# rpiSensors.net
KiCad netlist of a schematic drawn in EAGLE
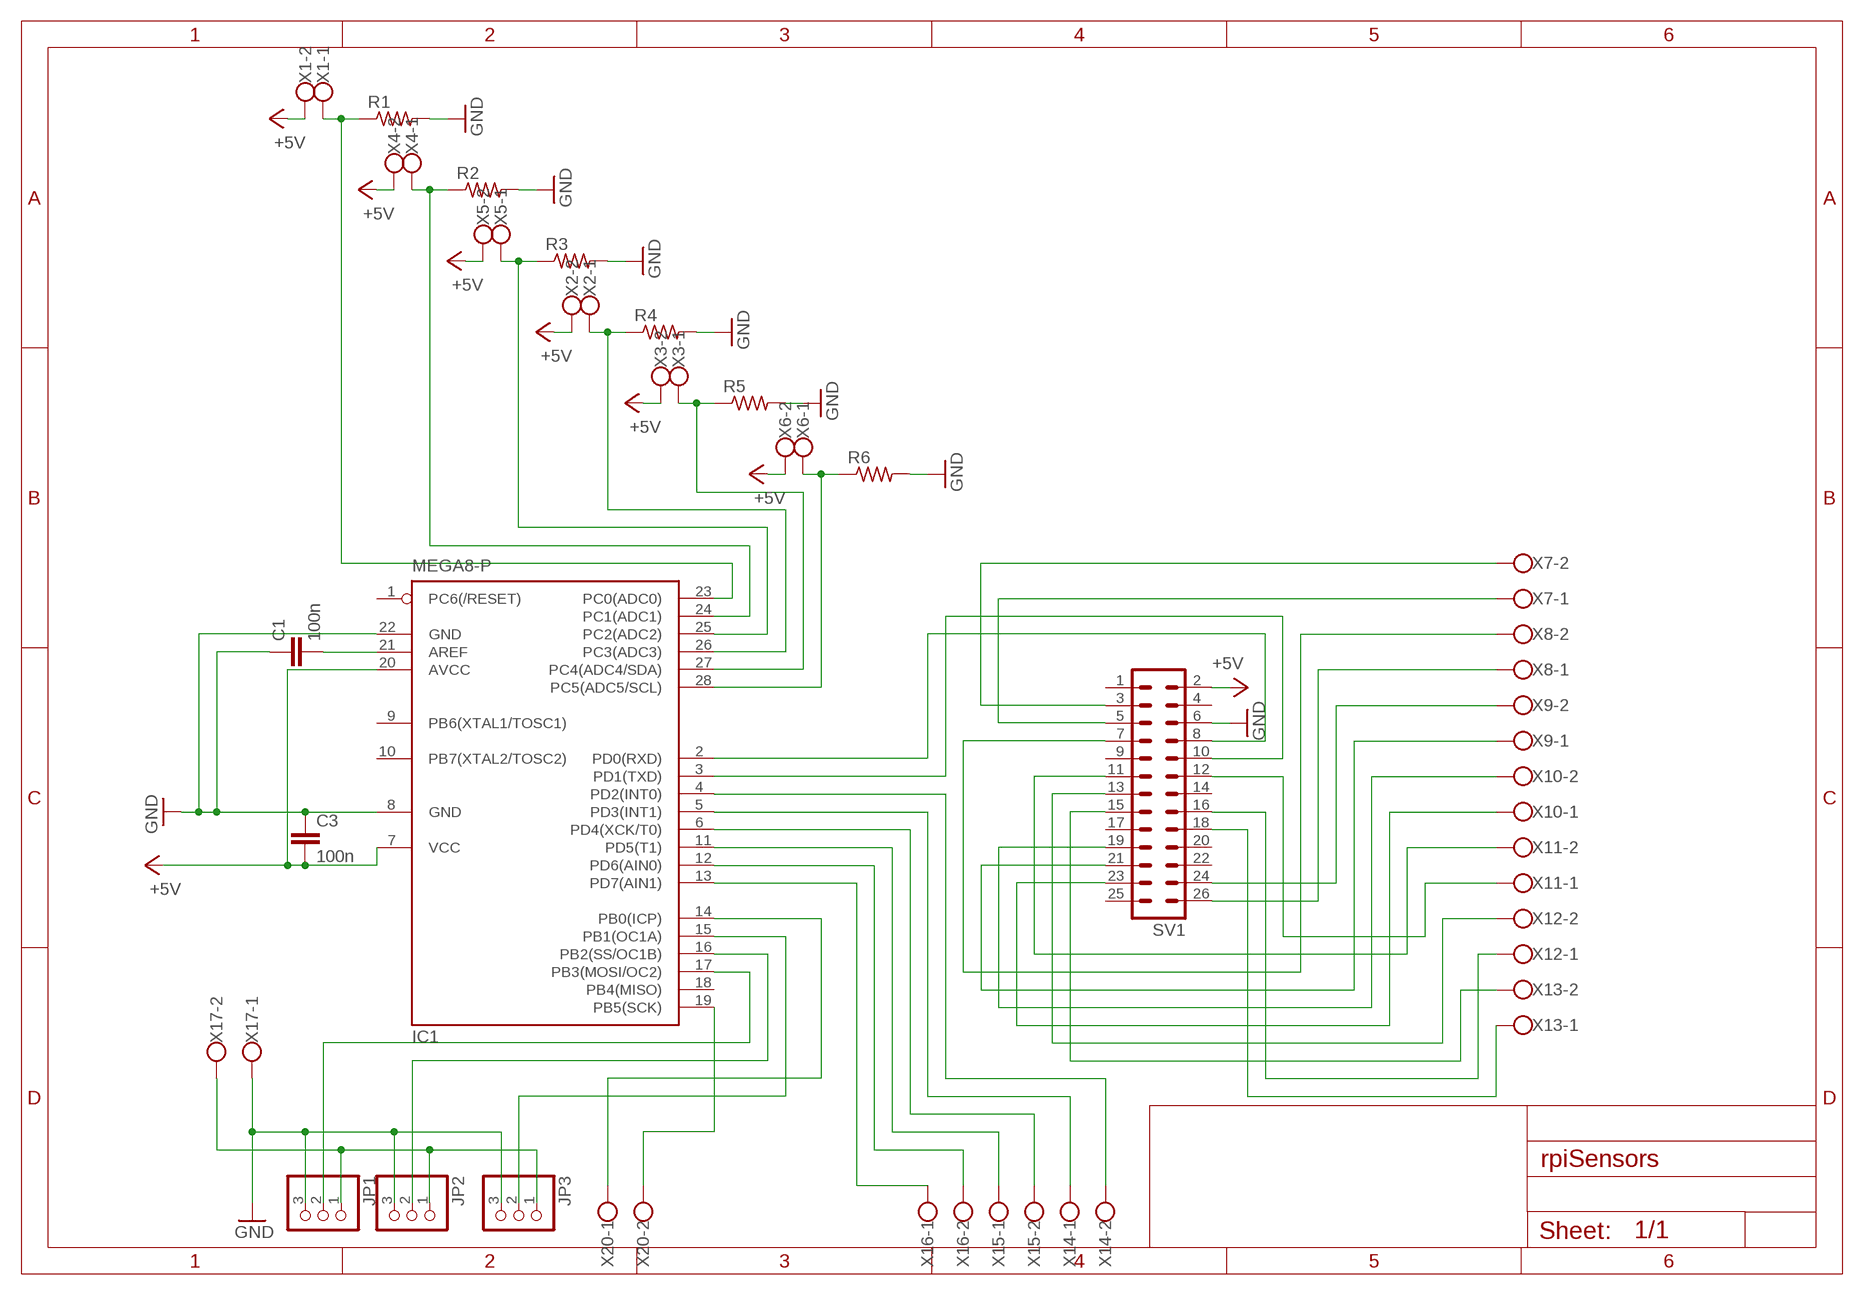
[diagram p0: schematic, sheet 1]

(export (version "E")
  (design (tool "Eeschema 10.0.6"))
  (components
    (comp (ref "C1")
      (value "100n")
      (footprint "eagle-import:C2.5-3")
      (libsource (lib "eagle-import") (part "C2,5-3"))
    )
    (comp (ref "C3")
      (value "100n")
      (footprint "eagle-import:C2.5-3")
      (libsource (lib "eagle-import") (part "C2,5-3"))
    )
    (comp (ref "IC1")
      (value "MEGA8-P")
      (footprint "eagle-import:DIL28-3")
      (libsource (lib "eagle-import") (part "MEGA8-P"))
    )
    (comp (ref "JP1")
      (value "PINHD-1X3")
      (footprint "eagle-import:1X03")
      (libsource (lib "eagle-import") (part "PINHD-1X3"))
    )
    (comp (ref "JP2")
      (value "PINHD-1X3")
      (footprint "eagle-import:1X03")
      (libsource (lib "eagle-import") (part "PINHD-1X3"))
    )
    (comp (ref "JP3")
      (value "PINHD-1X3")
      (footprint "eagle-import:1X03")
      (libsource (lib "eagle-import") (part "PINHD-1X3"))
    )
    (comp (ref "R1")
      (value "R-US_0309/12")
      (footprint "eagle-import:0309_12")
      (libsource (lib "eagle-import") (part "R-US_0309/12"))
    )
    (comp (ref "R2")
      (value "R-US_0309/12")
      (footprint "eagle-import:0309_12")
      (libsource (lib "eagle-import") (part "R-US_0309/12"))
    )
    (comp (ref "R3")
      (value "R-US_0309/12")
      (footprint "eagle-import:0309_12")
      (libsource (lib "eagle-import") (part "R-US_0309/12"))
    )
    (comp (ref "R4")
      (value "R-US_0309/12")
      (footprint "eagle-import:0309_12")
      (libsource (lib "eagle-import") (part "R-US_0309/12"))
    )
    (comp (ref "R5")
      (value "R-US_0309/12")
      (footprint "eagle-import:0309_12")
      (libsource (lib "eagle-import") (part "R-US_0309/12"))
    )
    (comp (ref "R6")
      (value "R-US_0309/12")
      (footprint "eagle-import:0309_12")
      (libsource (lib "eagle-import") (part "R-US_0309/12"))
    )
    (comp (ref "SV1")
      (value "ML26")
      (footprint "eagle-import:ML26")
      (libsource (lib "eagle-import") (part "ML26"))
    )
    (comp (ref "X1")
      (value "W237-102")
      (footprint "eagle-import:W237-102")
      (fields (field (name "MPN") "237-102"))
      (libsource (lib "eagle-import") (part "W237-102"))
    )
    (comp (ref "X2")
      (value "W237-102")
      (footprint "eagle-import:W237-102")
      (fields (field (name "MPN") "237-102"))
      (libsource (lib "eagle-import") (part "W237-102"))
    )
    (comp (ref "X3")
      (value "W237-102")
      (footprint "eagle-import:W237-102")
      (fields (field (name "MPN") "237-102"))
      (libsource (lib "eagle-import") (part "W237-102"))
    )
    (comp (ref "X4")
      (value "W237-102")
      (footprint "eagle-import:W237-102")
      (fields (field (name "MPN") "237-102"))
      (libsource (lib "eagle-import") (part "W237-102"))
    )
    (comp (ref "X5")
      (value "W237-102")
      (footprint "eagle-import:W237-102")
      (fields (field (name "MPN") "237-102"))
      (libsource (lib "eagle-import") (part "W237-102"))
    )
    (comp (ref "X6")
      (value "W237-102")
      (footprint "eagle-import:W237-102")
      (fields (field (name "MPN") "237-102"))
      (libsource (lib "eagle-import") (part "W237-102"))
    )
    (comp (ref "X7")
      (value "W237-102")
      (footprint "eagle-import:W237-102")
      (fields (field (name "MPN") "237-102"))
      (libsource (lib "eagle-import") (part "W237-102"))
    )
    (comp (ref "X8")
      (value "W237-102")
      (footprint "eagle-import:W237-102")
      (fields (field (name "MPN") "237-102"))
      (libsource (lib "eagle-import") (part "W237-102"))
    )
    (comp (ref "X9")
      (value "W237-102")
      (footprint "eagle-import:W237-102")
      (fields (field (name "MPN") "237-102"))
      (libsource (lib "eagle-import") (part "W237-102"))
    )
    (comp (ref "X10")
      (value "W237-102")
      (footprint "eagle-import:W237-102")
      (fields (field (name "MPN") "237-102"))
      (libsource (lib "eagle-import") (part "W237-102"))
    )
    (comp (ref "X11")
      (value "W237-102")
      (footprint "eagle-import:W237-102")
      (fields (field (name "MPN") "237-102"))
      (libsource (lib "eagle-import") (part "W237-102"))
    )
    (comp (ref "X12")
      (value "W237-102")
      (footprint "eagle-import:W237-102")
      (fields (field (name "MPN") "237-102"))
      (libsource (lib "eagle-import") (part "W237-102"))
    )
    (comp (ref "X13")
      (value "W237-102")
      (footprint "eagle-import:W237-102")
      (fields (field (name "MPN") "237-102"))
      (libsource (lib "eagle-import") (part "W237-102"))
    )
    (comp (ref "X14")
      (value "W237-102")
      (footprint "eagle-import:W237-102")
      (fields (field (name "MPN") "237-102"))
      (libsource (lib "eagle-import") (part "W237-102"))
    )
    (comp (ref "X15")
      (value "W237-102")
      (footprint "eagle-import:W237-102")
      (fields (field (name "MPN") "237-102"))
      (libsource (lib "eagle-import") (part "W237-102"))
    )
    (comp (ref "X16")
      (value "W237-102")
      (footprint "eagle-import:W237-102")
      (fields (field (name "MPN") "237-102"))
      (libsource (lib "eagle-import") (part "W237-102"))
    )
    (comp (ref "X17")
      (value "W237-102")
      (footprint "eagle-import:W237-102")
      (fields (field (name "MPN") "237-102"))
      (libsource (lib "eagle-import") (part "W237-102"))
    )
    (comp (ref "X20")
      (value "W237-102")
      (footprint "eagle-import:W237-102")
      (fields (field (name "MPN") "237-102"))
      (libsource (lib "eagle-import") (part "W237-102"))
    )
  )
  (nets
    (net (code "1") (name "+5V") (class "Default")
      (node (ref "C3") (pin "2") (pinfunction "2_2") (pintype "passive"))
      (node (ref "IC1") (pin "20") (pinfunction "AVCC_20") (pintype "power_in"))
      (node (ref "IC1") (pin "7") (pinfunction "VCC_7") (pintype "power_in"))
      (node (ref "SV1") (pin "2") (pinfunction "2_2") (pintype "passive"))
      (node (ref "X1") (pin "2") (pinfunction "KL_2") (pintype "passive"))
      (node (ref "X2") (pin "2") (pinfunction "KL_2") (pintype "passive"))
      (node (ref "X3") (pin "2") (pinfunction "KL_2") (pintype "passive"))
      (node (ref "X4") (pin "2") (pinfunction "KL_2") (pintype "passive"))
      (node (ref "X5") (pin "2") (pinfunction "KL_2") (pintype "passive"))
      (node (ref "X6") (pin "2") (pinfunction "KL_2") (pintype "passive"))
    )
    (net (code "2") (name "GND") (class "Default")
      (node (ref "C1") (pin "1") (pinfunction "1_1") (pintype "passive"))
      (node (ref "C3") (pin "1") (pinfunction "1_1") (pintype "passive"))
      (node (ref "IC1") (pin "22") (pinfunction "GND_22") (pintype "power_in"))
      (node (ref "IC1") (pin "8") (pinfunction "GND_8") (pintype "power_in"))
      (node (ref "JP1") (pin "3") (pinfunction "3_3") (pintype "passive"))
      (node (ref "JP2") (pin "3") (pinfunction "3_3") (pintype "passive"))
      (node (ref "JP3") (pin "3") (pinfunction "3_3") (pintype "passive"))
      (node (ref "R1") (pin "2") (pinfunction "2_2") (pintype "passive"))
      (node (ref "R2") (pin "2") (pinfunction "2_2") (pintype "passive"))
      (node (ref "R3") (pin "2") (pinfunction "2_2") (pintype "passive"))
      (node (ref "R4") (pin "2") (pinfunction "2_2") (pintype "passive"))
      (node (ref "R5") (pin "2") (pinfunction "2_2") (pintype "passive"))
      (node (ref "R6") (pin "2") (pinfunction "2_2") (pintype "passive"))
      (node (ref "SV1") (pin "6") (pinfunction "6_6") (pintype "passive"))
      (node (ref "X17") (pin "1") (pinfunction "KL_1") (pintype "passive"))
    )
    (net (code "3") (name "Net-(IC1-AREF)") (class "Default")
      (node (ref "C1") (pin "2") (pinfunction "2_2") (pintype "passive"))
      (node (ref "IC1") (pin "21") (pinfunction "AREF_21") (pintype "passive"))
    )
    (net (code "4") (name "Net-(IC1-PB0(ICP))") (class "Default")
      (node (ref "IC1") (pin "14") (pinfunction "PB0(ICP)_14") (pintype "bidirectional"))
      (node (ref "X20") (pin "1") (pinfunction "KL_1") (pintype "passive"))
    )
    (net (code "5") (name "Net-(IC1-PB1(OC1A))") (class "Default")
      (node (ref "IC1") (pin "15") (pinfunction "PB1(OC1A)_15") (pintype "bidirectional"))
      (node (ref "JP3") (pin "2") (pinfunction "2_2") (pintype "passive"))
    )
    (net (code "6") (name "Net-(IC1-PB2(SS{slash}OC1B))") (class "Default")
      (node (ref "IC1") (pin "16") (pinfunction "PB2(SS/OC1B)_16") (pintype "bidirectional"))
      (node (ref "JP2") (pin "2") (pinfunction "2_2") (pintype "passive"))
    )
    (net (code "7") (name "Net-(IC1-PB3(MOSI{slash}OC2))") (class "Default")
      (node (ref "IC1") (pin "17") (pinfunction "PB3(MOSI/OC2)_17") (pintype "bidirectional"))
      (node (ref "JP1") (pin "2") (pinfunction "2_2") (pintype "passive"))
    )
    (net (code "8") (name "Net-(IC1-PB5(SCK))") (class "Default")
      (node (ref "IC1") (pin "19") (pinfunction "PB5(SCK)_19") (pintype "bidirectional"))
      (node (ref "X20") (pin "2") (pinfunction "KL_2") (pintype "passive"))
    )
    (net (code "9") (name "Net-(IC1-PC0(ADC0))") (class "Default")
      (node (ref "IC1") (pin "23") (pinfunction "PC0(ADC0)_23") (pintype "bidirectional"))
      (node (ref "R1") (pin "1") (pinfunction "1_1") (pintype "passive"))
      (node (ref "X1") (pin "1") (pinfunction "KL_1") (pintype "passive"))
    )
    (net (code "10") (name "Net-(IC1-PC1(ADC1))") (class "Default")
      (node (ref "IC1") (pin "24") (pinfunction "PC1(ADC1)_24") (pintype "bidirectional"))
      (node (ref "R2") (pin "1") (pinfunction "1_1") (pintype "passive"))
      (node (ref "X4") (pin "1") (pinfunction "KL_1") (pintype "passive"))
    )
    (net (code "11") (name "Net-(IC1-PC2(ADC2))") (class "Default")
      (node (ref "IC1") (pin "25") (pinfunction "PC2(ADC2)_25") (pintype "bidirectional"))
      (node (ref "R3") (pin "1") (pinfunction "1_1") (pintype "passive"))
      (node (ref "X5") (pin "1") (pinfunction "KL_1") (pintype "passive"))
    )
    (net (code "12") (name "Net-(IC1-PC3(ADC3))") (class "Default")
      (node (ref "IC1") (pin "26") (pinfunction "PC3(ADC3)_26") (pintype "bidirectional"))
      (node (ref "R4") (pin "1") (pinfunction "1_1") (pintype "passive"))
      (node (ref "X2") (pin "1") (pinfunction "KL_1") (pintype "passive"))
    )
    (net (code "13") (name "Net-(IC1-PC4(ADC4{slash}SDA))") (class "Default")
      (node (ref "IC1") (pin "27") (pinfunction "PC4(ADC4/SDA)_27") (pintype "bidirectional"))
      (node (ref "R5") (pin "1") (pinfunction "1_1") (pintype "passive"))
      (node (ref "X3") (pin "1") (pinfunction "KL_1") (pintype "passive"))
    )
    (net (code "14") (name "Net-(IC1-PC5(ADC5{slash}SCL))") (class "Default")
      (node (ref "IC1") (pin "28") (pinfunction "PC5(ADC5/SCL)_28") (pintype "bidirectional"))
      (node (ref "R6") (pin "1") (pinfunction "1_1") (pintype "passive"))
      (node (ref "X6") (pin "1") (pinfunction "KL_1") (pintype "passive"))
    )
    (net (code "15") (name "Net-(IC1-PD0(RXD))") (class "Default")
      (node (ref "IC1") (pin "2") (pinfunction "PD0(RXD)_2") (pintype "bidirectional"))
      (node (ref "SV1") (pin "8") (pinfunction "8_8") (pintype "passive"))
    )
    (net (code "16") (name "Net-(IC1-PD1(TXD))") (class "Default")
      (node (ref "IC1") (pin "3") (pinfunction "PD1(TXD)_3") (pintype "bidirectional"))
      (node (ref "SV1") (pin "10") (pinfunction "10_10") (pintype "passive"))
    )
    (net (code "17") (name "Net-(IC1-PD2(INT0))") (class "Default")
      (node (ref "IC1") (pin "4") (pinfunction "PD2(INT0)_4") (pintype "bidirectional"))
      (node (ref "X14") (pin "2") (pinfunction "KL_2") (pintype "passive"))
    )
    (net (code "18") (name "Net-(IC1-PD3(INT1))") (class "Default")
      (node (ref "IC1") (pin "5") (pinfunction "PD3(INT1)_5") (pintype "bidirectional"))
      (node (ref "X14") (pin "1") (pinfunction "KL_1") (pintype "passive"))
    )
    (net (code "19") (name "Net-(IC1-PD4(XCK{slash}T0))") (class "Default")
      (node (ref "IC1") (pin "6") (pinfunction "PD4(XCK/T0)_6") (pintype "bidirectional"))
      (node (ref "X15") (pin "2") (pinfunction "KL_2") (pintype "passive"))
    )
    (net (code "20") (name "Net-(IC1-PD5(T1))") (class "Default")
      (node (ref "IC1") (pin "11") (pinfunction "PD5(T1)_11") (pintype "bidirectional"))
      (node (ref "X15") (pin "1") (pinfunction "KL_1") (pintype "passive"))
    )
    (net (code "21") (name "Net-(IC1-PD6(AIN0))") (class "Default")
      (node (ref "IC1") (pin "12") (pinfunction "PD6(AIN0)_12") (pintype "bidirectional"))
      (node (ref "X16") (pin "2") (pinfunction "KL_2") (pintype "passive"))
    )
    (net (code "22") (name "Net-(IC1-PD7(AIN1))") (class "Default")
      (node (ref "IC1") (pin "13") (pinfunction "PD7(AIN1)_13") (pintype "bidirectional"))
      (node (ref "X16") (pin "1") (pinfunction "KL_1") (pintype "passive"))
    )
    (net (code "23") (name "Net-(X7A-KL)") (class "Default")
      (node (ref "SV1") (pin "5") (pinfunction "5_5") (pintype "passive"))
      (node (ref "X7") (pin "1") (pinfunction "KL_1") (pintype "passive"))
    )
    (net (code "24") (name "Net-(X7B-KL)") (class "Default")
      (node (ref "SV1") (pin "3") (pinfunction "3_3") (pintype "passive"))
      (node (ref "X7") (pin "2") (pinfunction "KL_2") (pintype "passive"))
    )
    (net (code "25") (name "Net-(X8A-KL)") (class "Default")
      (node (ref "SV1") (pin "26") (pinfunction "26_26") (pintype "passive"))
      (node (ref "X8") (pin "1") (pinfunction "KL_1") (pintype "passive"))
    )
    (net (code "26") (name "Net-(X8B-KL)") (class "Default")
      (node (ref "SV1") (pin "7") (pinfunction "7_7") (pintype "passive"))
      (node (ref "X8") (pin "2") (pinfunction "KL_2") (pintype "passive"))
    )
    (net (code "27") (name "Net-(X9A-KL)") (class "Default")
      (node (ref "SV1") (pin "21") (pinfunction "21_21") (pintype "passive"))
      (node (ref "X9") (pin "1") (pinfunction "KL_1") (pintype "passive"))
    )
    (net (code "28") (name "Net-(X9B-KL)") (class "Default")
      (node (ref "SV1") (pin "24") (pinfunction "24_24") (pintype "passive"))
      (node (ref "X9") (pin "2") (pinfunction "KL_2") (pintype "passive"))
    )
    (net (code "29") (name "Net-(X10A-KL)") (class "Default")
      (node (ref "SV1") (pin "23") (pinfunction "23_23") (pintype "passive"))
      (node (ref "X10") (pin "1") (pinfunction "KL_1") (pintype "passive"))
    )
    (net (code "30") (name "Net-(X10B-KL)") (class "Default")
      (node (ref "SV1") (pin "19") (pinfunction "19_19") (pintype "passive"))
      (node (ref "X10") (pin "2") (pinfunction "KL_2") (pintype "passive"))
    )
    (net (code "31") (name "Net-(X11A-KL)") (class "Default")
      (node (ref "SV1") (pin "12") (pinfunction "12_12") (pintype "passive"))
      (node (ref "X11") (pin "1") (pinfunction "KL_1") (pintype "passive"))
    )
    (net (code "32") (name "Net-(X11B-KL)") (class "Default")
      (node (ref "SV1") (pin "11") (pinfunction "11_11") (pintype "passive"))
      (node (ref "X11") (pin "2") (pinfunction "KL_2") (pintype "passive"))
    )
    (net (code "33") (name "Net-(X12A-KL)") (class "Default")
      (node (ref "SV1") (pin "16") (pinfunction "16_16") (pintype "passive"))
      (node (ref "X12") (pin "1") (pinfunction "KL_1") (pintype "passive"))
    )
    (net (code "34") (name "Net-(X12B-KL)") (class "Default")
      (node (ref "SV1") (pin "13") (pinfunction "13_13") (pintype "passive"))
      (node (ref "X12") (pin "2") (pinfunction "KL_2") (pintype "passive"))
    )
    (net (code "35") (name "Net-(X13A-KL)") (class "Default")
      (node (ref "SV1") (pin "18") (pinfunction "18_18") (pintype "passive"))
      (node (ref "X13") (pin "1") (pinfunction "KL_1") (pintype "passive"))
    )
    (net (code "36") (name "Net-(X13B-KL)") (class "Default")
      (node (ref "SV1") (pin "15") (pinfunction "15_15") (pintype "passive"))
      (node (ref "X13") (pin "2") (pinfunction "KL_2") (pintype "passive"))
    )
    (net (code "37") (name "Net-(X17B-KL)") (class "Default")
      (node (ref "JP1") (pin "1") (pinfunction "1_1") (pintype "passive"))
      (node (ref "JP2") (pin "1") (pinfunction "1_1") (pintype "passive"))
      (node (ref "JP3") (pin "1") (pinfunction "1_1") (pintype "passive"))
      (node (ref "X17") (pin "2") (pinfunction "KL_2") (pintype "passive"))
    )
    (net (code "38") (name "unconnected-(IC1-PB4(MISO)-Pad18)") (class "Default")
      (node (ref "IC1") (pin "18") (pinfunction "PB4(MISO)_18") (pintype "bidirectional"))
    )
    (net (code "39") (name "unconnected-(IC1-PB6(XTAL1{slash}TOSC1)-Pad9)") (class "Default")
      (node (ref "IC1") (pin "9") (pinfunction "PB6(XTAL1/TOSC1)_9") (pintype "bidirectional"))
    )
    (net (code "40") (name "unconnected-(IC1-PB7(XTAL2{slash}TOSC2)-Pad10)") (class "Default")
      (node (ref "IC1") (pin "10") (pinfunction "PB7(XTAL2/TOSC2)_10") (pintype "bidirectional"))
    )
    (net (code "41") (name "unconnected-(IC1-PC6({slash}RESET)-Pad1)") (class "Default")
      (node (ref "IC1") (pin "1") (pinfunction "PC6(/RESET)_1") (pintype "bidirectional"))
    )
    (net (code "42") (name "unconnected-(SV1-Pad1)") (class "Default")
      (node (ref "SV1") (pin "1") (pinfunction "1_1") (pintype "passive"))
    )
    (net (code "43") (name "unconnected-(SV1-Pad4)") (class "Default")
      (node (ref "SV1") (pin "4") (pinfunction "4_4") (pintype "passive"))
    )
    (net (code "44") (name "unconnected-(SV1-Pad9)") (class "Default")
      (node (ref "SV1") (pin "9") (pinfunction "9_9") (pintype "passive"))
    )
    (net (code "45") (name "unconnected-(SV1-Pad14)") (class "Default")
      (node (ref "SV1") (pin "14") (pinfunction "14_14") (pintype "passive"))
    )
    (net (code "46") (name "unconnected-(SV1-Pad17)") (class "Default")
      (node (ref "SV1") (pin "17") (pinfunction "17_17") (pintype "passive"))
    )
    (net (code "47") (name "unconnected-(SV1-Pad20)") (class "Default")
      (node (ref "SV1") (pin "20") (pinfunction "20_20") (pintype "passive"))
    )
    (net (code "48") (name "unconnected-(SV1-Pad22)") (class "Default")
      (node (ref "SV1") (pin "22") (pinfunction "22_22") (pintype "passive"))
    )
    (net (code "49") (name "unconnected-(SV1-Pad25)") (class "Default")
      (node (ref "SV1") (pin "25") (pinfunction "25_25") (pintype "passive"))
    )
  )
)
